# gamepad.net
KiCad netlist of a schematic drawn in EasyEDA Pro
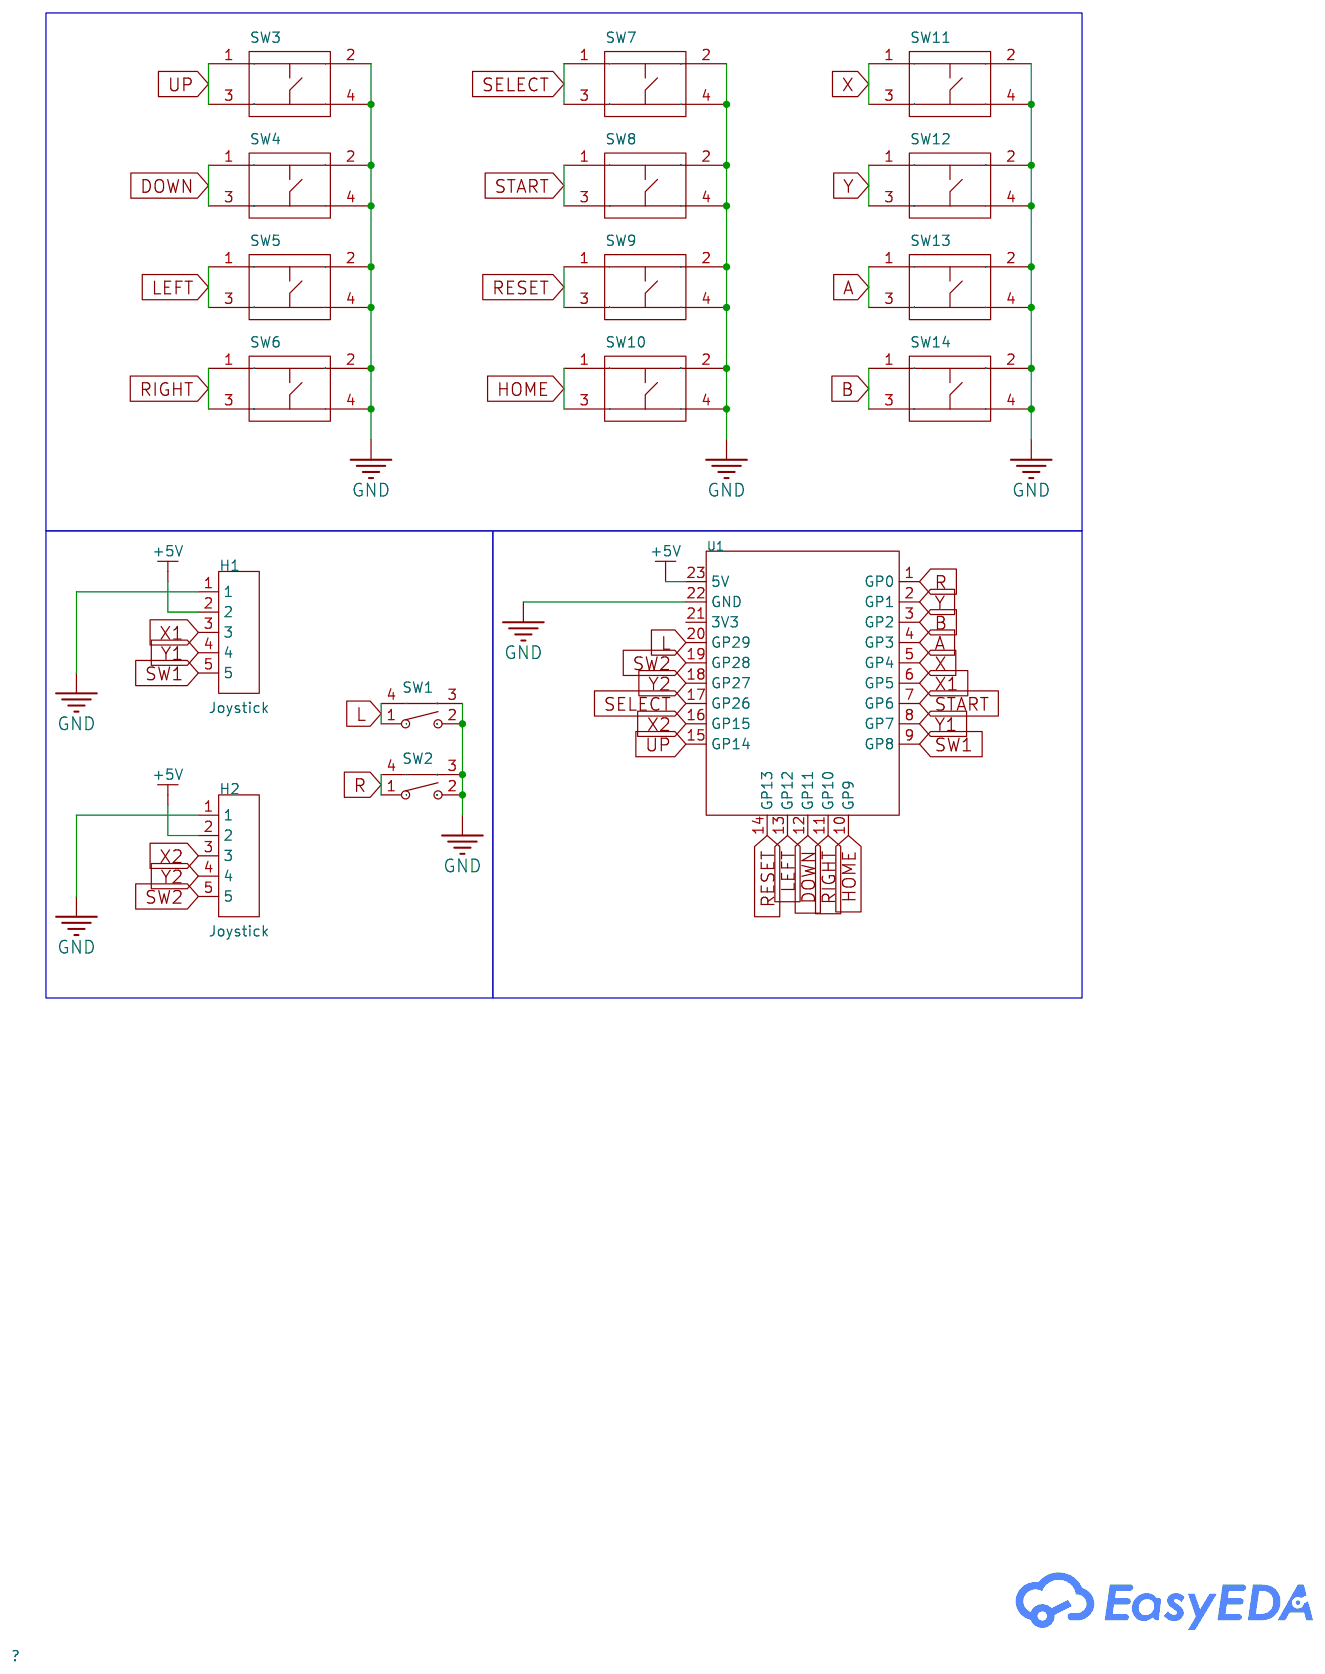
[diagram p0: schematic sheet]

(export (version "E")
  (design (tool "Eeschema 10.0.6"))
  (components
    (comp (ref "H1")
      (value "Joystick")
      (footprint "easyedapro:HDR-TH_5P-P2.54_HTSW-105-08-F-S")
      (fields (field (name "Manufacturer") "SAMTEC"))
      (libsource (lib "easyedapro") (part "MTSW-105-22-F-S-370"))
    )
    (comp (ref "H2")
      (value "Joystick")
      (footprint "easyedapro:HDR-TH_5P-P2.54_HTSW-105-08-F-S")
      (fields (field (name "Manufacturer") "SAMTEC"))
      (libsource (lib "easyedapro") (part "MTSW-105-22-F-S-370"))
    )
    (comp (ref "SW1")
      (value "K2-1102AQ-H4CW-01")
      (footprint "easyedapro:SW-TH_K2-1102BQ-G4CW-01")
      (fields (field (name "Manufacturer") "韩国韩荣"))
      (libsource (lib "easyedapro") (part "K2-1102AQ-H4CW-01"))
    )
    (comp (ref "SW2")
      (value "K2-1102AQ-H4CW-01")
      (footprint "easyedapro:SW-TH_K2-1102BQ-G4CW-01")
      (fields (field (name "Manufacturer") "韩国韩荣"))
      (libsource (lib "easyedapro") (part "K2-1102AQ-H4CW-01"))
    )
    (comp (ref "SW3")
      (value "K2-1102DP-C4SW-04")
      (footprint "easyedapro:KEY-TH_4P-L6.0-W6.0-P4.50-LS6.50")
      (fields (field (name "Manufacturer") "韩国韩荣"))
      (libsource (lib "easyedapro") (part "K2-1102DP-C4SW-04"))
    )
    (comp (ref "SW4")
      (value "K2-1102DP-C4SW-04")
      (footprint "easyedapro:KEY-TH_4P-L6.0-W6.0-P4.50-LS6.50")
      (fields (field (name "Manufacturer") "韩国韩荣"))
      (libsource (lib "easyedapro") (part "K2-1102DP-C4SW-04"))
    )
    (comp (ref "SW5")
      (value "K2-1102DP-C4SW-04")
      (footprint "easyedapro:KEY-TH_4P-L6.0-W6.0-P4.50-LS6.50")
      (fields (field (name "Manufacturer") "韩国韩荣"))
      (libsource (lib "easyedapro") (part "K2-1102DP-C4SW-04"))
    )
    (comp (ref "SW6")
      (value "K2-1102DP-C4SW-04")
      (footprint "easyedapro:KEY-TH_4P-L6.0-W6.0-P4.50-LS6.50")
      (fields (field (name "Manufacturer") "韩国韩荣"))
      (libsource (lib "easyedapro") (part "K2-1102DP-C4SW-04"))
    )
    (comp (ref "SW7")
      (value "K2-1102DP-C4SW-04")
      (footprint "easyedapro:KEY-TH_4P-L6.0-W6.0-P4.50-LS6.50")
      (fields (field (name "Manufacturer") "韩国韩荣"))
      (libsource (lib "easyedapro") (part "K2-1102DP-C4SW-04"))
    )
    (comp (ref "SW8")
      (value "K2-1102DP-C4SW-04")
      (footprint "easyedapro:KEY-TH_4P-L6.0-W6.0-P4.50-LS6.50")
      (fields (field (name "Manufacturer") "韩国韩荣"))
      (libsource (lib "easyedapro") (part "K2-1102DP-C4SW-04"))
    )
    (comp (ref "SW9")
      (value "K2-1102DP-C4SW-04")
      (footprint "easyedapro:KEY-TH_4P-L6.0-W6.0-P4.50-LS6.50")
      (fields (field (name "Manufacturer") "韩国韩荣"))
      (libsource (lib "easyedapro") (part "K2-1102DP-C4SW-04"))
    )
    (comp (ref "SW10")
      (value "K2-1102DP-C4SW-04")
      (footprint "easyedapro:KEY-TH_4P-L6.0-W6.0-P4.50-LS6.50")
      (fields (field (name "Manufacturer") "韩国韩荣"))
      (libsource (lib "easyedapro") (part "K2-1102DP-C4SW-04"))
    )
    (comp (ref "SW11")
      (value "K2-1102DP-C4SW-04")
      (footprint "easyedapro:KEY-TH_4P-L6.0-W6.0-P4.50-LS6.50")
      (fields (field (name "Manufacturer") "韩国韩荣"))
      (libsource (lib "easyedapro") (part "K2-1102DP-C4SW-04"))
    )
    (comp (ref "SW12")
      (value "K2-1102DP-C4SW-04")
      (footprint "easyedapro:KEY-TH_4P-L6.0-W6.0-P4.50-LS6.50")
      (fields (field (name "Manufacturer") "韩国韩荣"))
      (libsource (lib "easyedapro") (part "K2-1102DP-C4SW-04"))
    )
    (comp (ref "SW13")
      (value "K2-1102DP-C4SW-04")
      (footprint "easyedapro:KEY-TH_4P-L6.0-W6.0-P4.50-LS6.50")
      (fields (field (name "Manufacturer") "韩国韩荣"))
      (libsource (lib "easyedapro") (part "K2-1102DP-C4SW-04"))
    )
    (comp (ref "SW14")
      (value "K2-1102DP-C4SW-04")
      (footprint "easyedapro:KEY-TH_4P-L6.0-W6.0-P4.50-LS6.50")
      (fields (field (name "Manufacturer") "韩国韩荣"))
      (libsource (lib "easyedapro") (part "K2-1102DP-C4SW-04"))
    )
    (comp (ref "U1")
      (value "RP2040-Zero")
      (footprint "easyedapro:COMM-SMD_RP2040-ZERO")
      (fields (field (name "Manufacturer") "Waveshare(微雪电子)"))
      (libsource (lib "easyedapro") (part "RP2040-ZERO"))
    )
  )
  (nets
    (net (code "1") (name "+5V") (class "Default")
      (node (ref "H1") (pin "2") (pinfunction "2_2") (pintype "unspecified"))
      (node (ref "H2") (pin "2") (pinfunction "2_2") (pintype "unspecified"))
      (node (ref "U1") (pin "23") (pinfunction "5V_23") (pintype "input"))
    )
    (net (code "2") (name "A") (class "Default")
      (node (ref "SW13") (pin "1") (pinfunction "1_1") (pintype "unspecified"))
      (node (ref "SW13") (pin "3") (pinfunction "3_3") (pintype "unspecified"))
      (node (ref "U1") (pin "4") (pinfunction "GP3_4") (pintype "input"))
    )
    (net (code "3") (name "B") (class "Default")
      (node (ref "SW14") (pin "1") (pinfunction "1_1") (pintype "unspecified"))
      (node (ref "SW14") (pin "3") (pinfunction "3_3") (pintype "unspecified"))
      (node (ref "U1") (pin "3") (pinfunction "GP2_3") (pintype "input"))
    )
    (net (code "4") (name "DOWN") (class "Default")
      (node (ref "SW4") (pin "1") (pinfunction "1_1") (pintype "unspecified"))
      (node (ref "SW4") (pin "3") (pinfunction "3_3") (pintype "unspecified"))
      (node (ref "U1") (pin "12") (pinfunction "GP11_12") (pintype "input"))
    )
    (net (code "5") (name "GND") (class "Default")
      (node (ref "H1") (pin "1") (pinfunction "1_1") (pintype "unspecified"))
      (node (ref "H2") (pin "1") (pinfunction "1_1") (pintype "unspecified"))
      (node (ref "SW1") (pin "2") (pinfunction "2_2") (pintype "input"))
      (node (ref "SW1") (pin "3") (pinfunction "3_3") (pintype "input"))
      (node (ref "SW10") (pin "2") (pinfunction "2_2") (pintype "unspecified"))
      (node (ref "SW10") (pin "4") (pinfunction "4_4") (pintype "unspecified"))
      (node (ref "SW11") (pin "2") (pinfunction "2_2") (pintype "unspecified"))
      (node (ref "SW11") (pin "4") (pinfunction "4_4") (pintype "unspecified"))
      (node (ref "SW12") (pin "2") (pinfunction "2_2") (pintype "unspecified"))
      (node (ref "SW12") (pin "4") (pinfunction "4_4") (pintype "unspecified"))
      (node (ref "SW13") (pin "2") (pinfunction "2_2") (pintype "unspecified"))
      (node (ref "SW13") (pin "4") (pinfunction "4_4") (pintype "unspecified"))
      (node (ref "SW14") (pin "2") (pinfunction "2_2") (pintype "unspecified"))
      (node (ref "SW14") (pin "4") (pinfunction "4_4") (pintype "unspecified"))
      (node (ref "SW2") (pin "2") (pinfunction "2_2") (pintype "input"))
      (node (ref "SW2") (pin "3") (pinfunction "3_3") (pintype "input"))
      (node (ref "SW3") (pin "2") (pinfunction "2_2") (pintype "unspecified"))
      (node (ref "SW3") (pin "4") (pinfunction "4_4") (pintype "unspecified"))
      (node (ref "SW4") (pin "2") (pinfunction "2_2") (pintype "unspecified"))
      (node (ref "SW4") (pin "4") (pinfunction "4_4") (pintype "unspecified"))
      (node (ref "SW5") (pin "2") (pinfunction "2_2") (pintype "unspecified"))
      (node (ref "SW5") (pin "4") (pinfunction "4_4") (pintype "unspecified"))
      (node (ref "SW6") (pin "2") (pinfunction "2_2") (pintype "unspecified"))
      (node (ref "SW6") (pin "4") (pinfunction "4_4") (pintype "unspecified"))
      (node (ref "SW7") (pin "2") (pinfunction "2_2") (pintype "unspecified"))
      (node (ref "SW7") (pin "4") (pinfunction "4_4") (pintype "unspecified"))
      (node (ref "SW8") (pin "2") (pinfunction "2_2") (pintype "unspecified"))
      (node (ref "SW8") (pin "4") (pinfunction "4_4") (pintype "unspecified"))
      (node (ref "SW9") (pin "2") (pinfunction "2_2") (pintype "unspecified"))
      (node (ref "SW9") (pin "4") (pinfunction "4_4") (pintype "unspecified"))
      (node (ref "U1") (pin "22") (pinfunction "GND_22") (pintype "input"))
    )
    (net (code "6") (name "HOME") (class "Default")
      (node (ref "SW10") (pin "1") (pinfunction "1_1") (pintype "unspecified"))
      (node (ref "SW10") (pin "3") (pinfunction "3_3") (pintype "unspecified"))
      (node (ref "U1") (pin "10") (pinfunction "GP9_10") (pintype "input"))
    )
    (net (code "7") (name "L") (class "Default")
      (node (ref "SW1") (pin "1") (pinfunction "1_1") (pintype "input"))
      (node (ref "SW1") (pin "4") (pinfunction "4_4") (pintype "input"))
      (node (ref "U1") (pin "20") (pinfunction "GP29_20") (pintype "input"))
    )
    (net (code "8") (name "LEFT") (class "Default")
      (node (ref "SW5") (pin "1") (pinfunction "1_1") (pintype "unspecified"))
      (node (ref "SW5") (pin "3") (pinfunction "3_3") (pintype "unspecified"))
      (node (ref "U1") (pin "13") (pinfunction "GP12_13") (pintype "input"))
    )
    (net (code "9") (name "R") (class "Default")
      (node (ref "SW2") (pin "1") (pinfunction "1_1") (pintype "input"))
      (node (ref "SW2") (pin "4") (pinfunction "4_4") (pintype "input"))
      (node (ref "U1") (pin "1") (pinfunction "GP0_1") (pintype "input"))
    )
    (net (code "10") (name "RESET") (class "Default")
      (node (ref "SW9") (pin "1") (pinfunction "1_1") (pintype "unspecified"))
      (node (ref "SW9") (pin "3") (pinfunction "3_3") (pintype "unspecified"))
      (node (ref "U1") (pin "14") (pinfunction "GP13_14") (pintype "input"))
    )
    (net (code "11") (name "RIGHT") (class "Default")
      (node (ref "SW6") (pin "1") (pinfunction "1_1") (pintype "unspecified"))
      (node (ref "SW6") (pin "3") (pinfunction "3_3") (pintype "unspecified"))
      (node (ref "U1") (pin "11") (pinfunction "GP10_11") (pintype "input"))
    )
    (net (code "12") (name "SELECT") (class "Default")
      (node (ref "SW7") (pin "1") (pinfunction "1_1") (pintype "unspecified"))
      (node (ref "SW7") (pin "3") (pinfunction "3_3") (pintype "unspecified"))
      (node (ref "U1") (pin "17") (pinfunction "GP26_17") (pintype "input"))
    )
    (net (code "13") (name "START") (class "Default")
      (node (ref "SW8") (pin "1") (pinfunction "1_1") (pintype "unspecified"))
      (node (ref "SW8") (pin "3") (pinfunction "3_3") (pintype "unspecified"))
      (node (ref "U1") (pin "7") (pinfunction "GP6_7") (pintype "input"))
    )
    (net (code "14") (name "SW1") (class "Default")
      (node (ref "H1") (pin "5") (pinfunction "5_5") (pintype "unspecified"))
      (node (ref "U1") (pin "9") (pinfunction "GP8_9") (pintype "input"))
    )
    (net (code "15") (name "SW2") (class "Default")
      (node (ref "H2") (pin "5") (pinfunction "5_5") (pintype "unspecified"))
      (node (ref "U1") (pin "19") (pinfunction "GP28_19") (pintype "input"))
    )
    (net (code "16") (name "UP") (class "Default")
      (node (ref "SW3") (pin "1") (pinfunction "1_1") (pintype "unspecified"))
      (node (ref "SW3") (pin "3") (pinfunction "3_3") (pintype "unspecified"))
      (node (ref "U1") (pin "15") (pinfunction "GP14_15") (pintype "input"))
    )
    (net (code "17") (name "X") (class "Default")
      (node (ref "SW11") (pin "1") (pinfunction "1_1") (pintype "unspecified"))
      (node (ref "SW11") (pin "3") (pinfunction "3_3") (pintype "unspecified"))
      (node (ref "U1") (pin "5") (pinfunction "GP4_5") (pintype "input"))
    )
    (net (code "18") (name "X1") (class "Default")
      (node (ref "H1") (pin "3") (pinfunction "3_3") (pintype "unspecified"))
      (node (ref "U1") (pin "6") (pinfunction "GP5_6") (pintype "input"))
    )
    (net (code "19") (name "X2") (class "Default")
      (node (ref "H2") (pin "3") (pinfunction "3_3") (pintype "unspecified"))
      (node (ref "U1") (pin "16") (pinfunction "GP15_16") (pintype "input"))
    )
    (net (code "20") (name "Y") (class "Default")
      (node (ref "SW12") (pin "1") (pinfunction "1_1") (pintype "unspecified"))
      (node (ref "SW12") (pin "3") (pinfunction "3_3") (pintype "unspecified"))
      (node (ref "U1") (pin "2") (pinfunction "GP1_2") (pintype "input"))
    )
    (net (code "21") (name "Y1") (class "Default")
      (node (ref "H1") (pin "4") (pinfunction "4_4") (pintype "unspecified"))
      (node (ref "U1") (pin "8") (pinfunction "GP7_8") (pintype "input"))
    )
    (net (code "22") (name "Y2") (class "Default")
      (node (ref "H2") (pin "4") (pinfunction "4_4") (pintype "unspecified"))
      (node (ref "U1") (pin "18") (pinfunction "GP27_18") (pintype "input"))
    )
    (net (code "23") (name "unconnected-(U1-3V3-Pad21)") (class "Default")
      (node (ref "U1") (pin "21") (pinfunction "3V3_21") (pintype "input"))
    )
  )
)
